# MB1167.net
KiCad netlist of a schematic drawn in Altium Designer
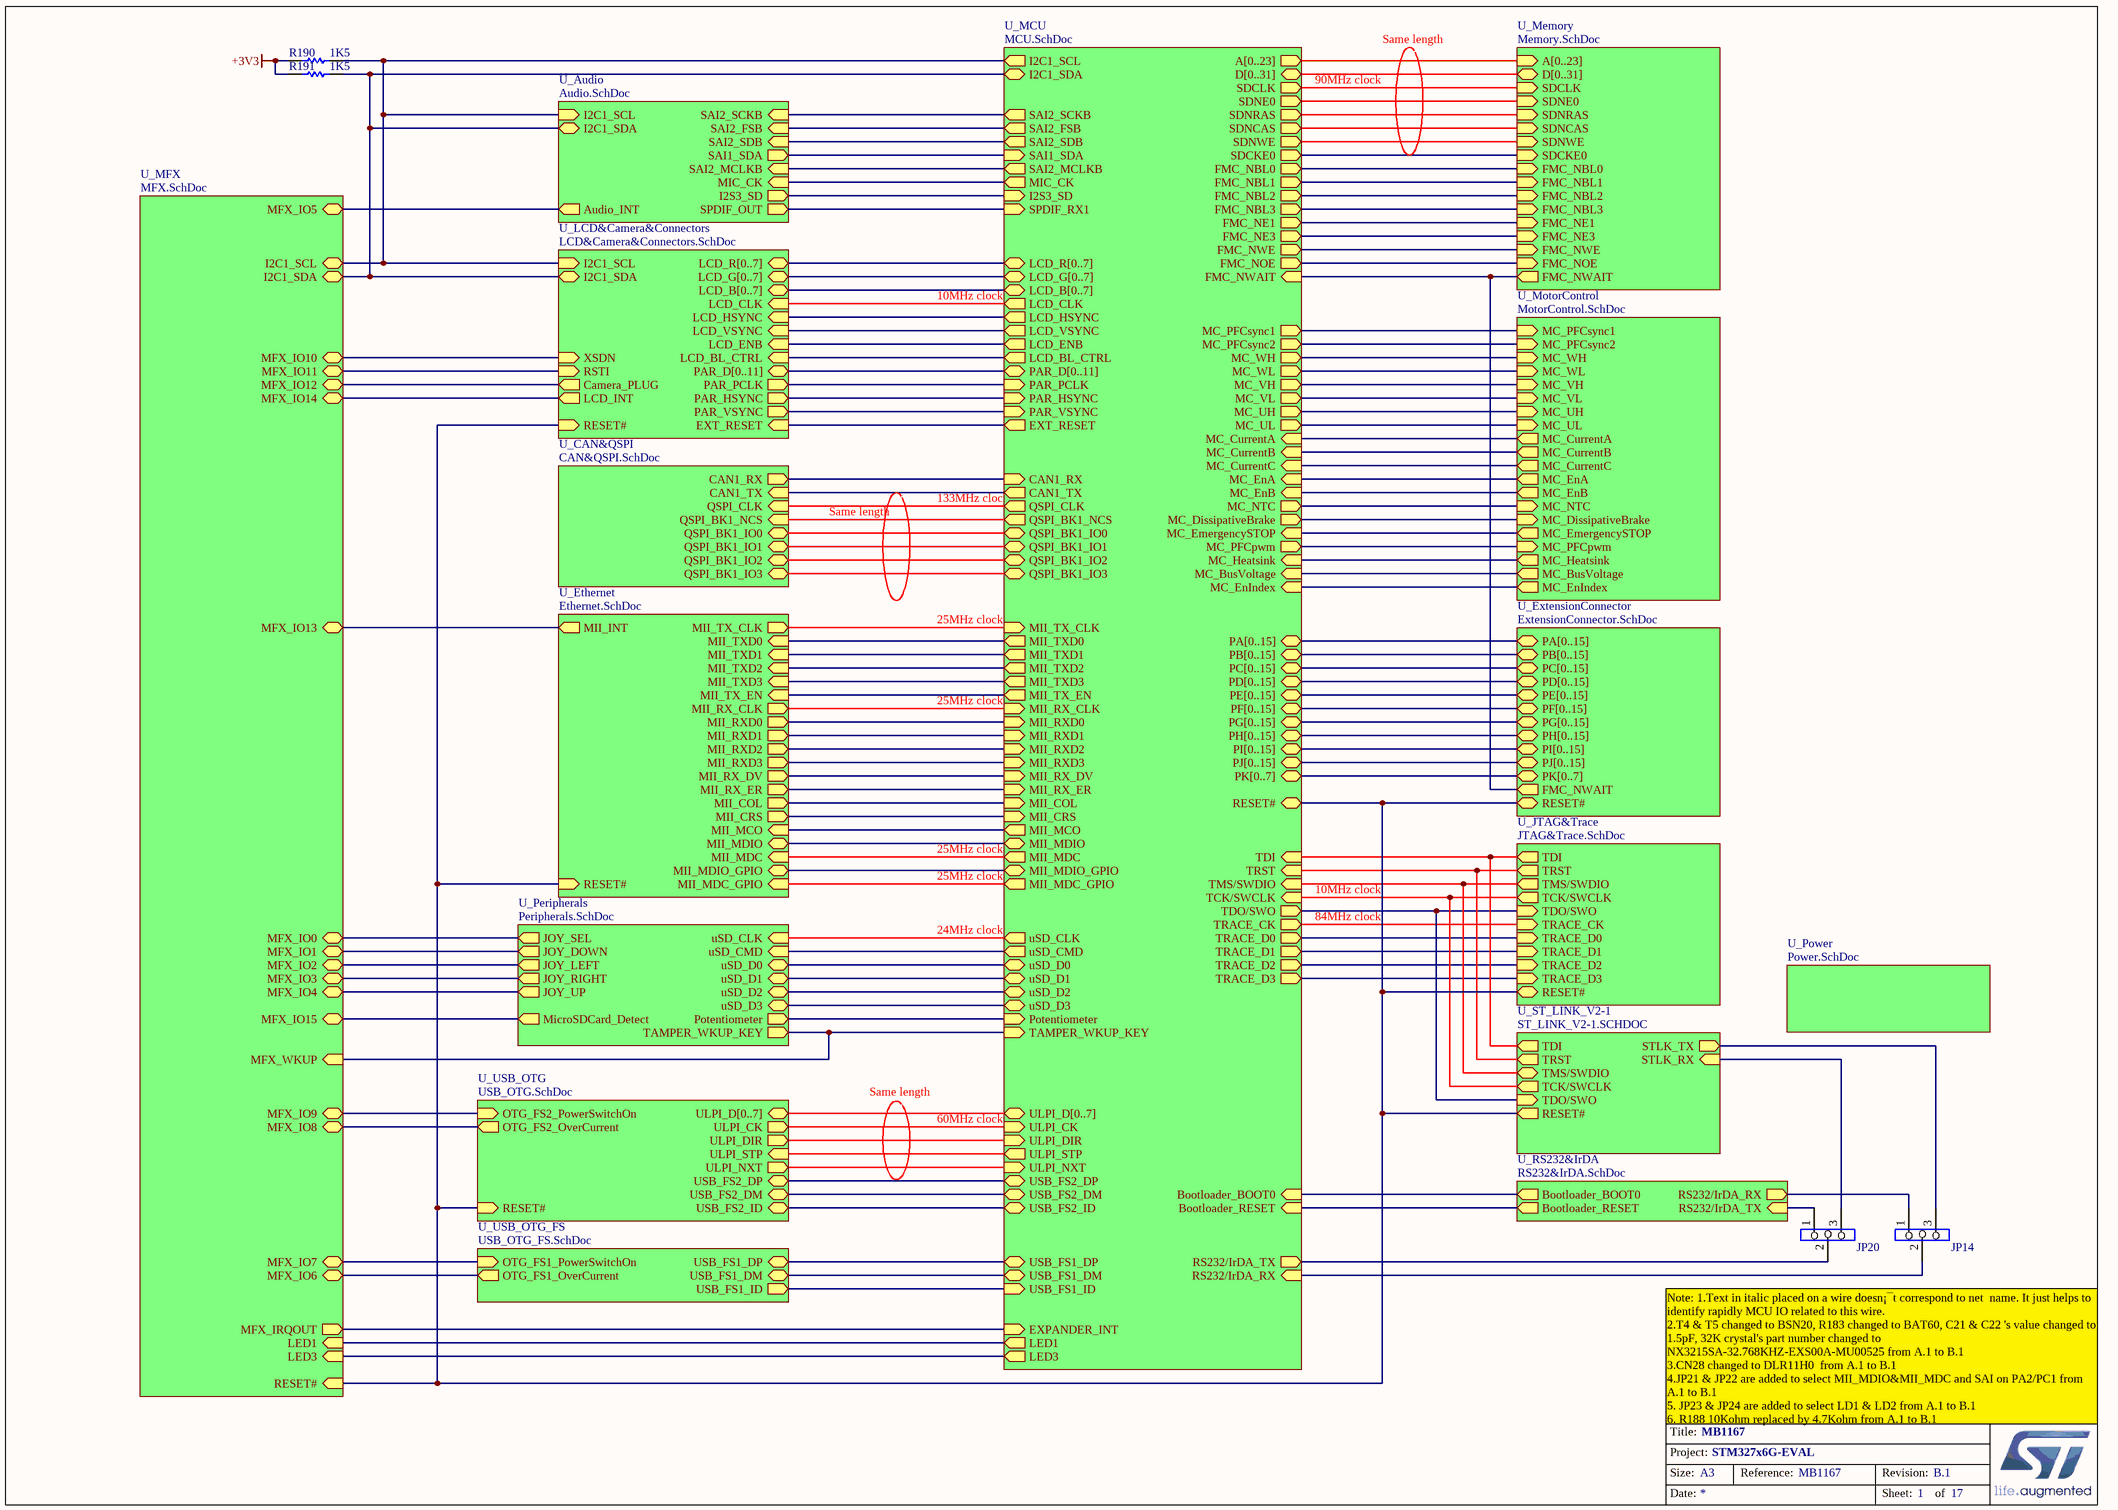
[diagram p0: MB1167.SchDoc]

(export (version "E")
  (design (tool "Eeschema 10.0.6"))
  (components
    (comp (ref "JP14") (value "~") (footprint "SIP3") (libsource (lib "STR910_SCHLIB") (part "Jumper3")))
    (comp (ref "JP20") (value "~") (footprint "SIP3") (libsource (lib "STR910_SCHLIB") (part "Jumper3")))
    (comp (ref "R190")
      (value "1K5")
      (footprint "0603R")
      (description "Resistor")
      (fields (field (name "PUBLISHER") "Altium Limited"))
      (libsource (lib "Miscellaneous Devices") (part "Res1"))
    )
    (comp (ref "R191")
      (value "1K5")
      (footprint "0603R")
      (description "Resistor")
      (fields (field (name "PUBLISHER") "Altium Limited"))
      (libsource (lib "Miscellaneous Devices") (part "Res1"))
    )
  )
  (nets
    (net (code "1") (name "+3V3") (class "Default")
      (node (ref "R190") (pin "1") (pinfunction "1_1") (pintype "passive"))
      (node (ref "R191") (pin "1") (pinfunction "1_1") (pintype "passive"))
    )
    (net (code "20") (name "/I2C1_SCL") (class "Default")
      (node (ref "R190") (pin "2") (pinfunction "2_2") (pintype "passive"))
    )
    (net (code "21") (name "/I2C1_SDA") (class "Default")
      (node (ref "R191") (pin "2") (pinfunction "2_2") (pintype "passive"))
    )
    (net (code "112") (name "/RS232{slash}IrDA_RX") (class "Default")
      (node (ref "JP14") (pin "1") (pintype "passive"))
    )
    (net (code "113") (name "/RS232{slash}IrDA_RX_1") (class "Default")
      (node (ref "JP14") (pin "2") (pintype "passive"))
    )
    (net (code "114") (name "/RS232{slash}IrDA_TX") (class "Default")
      (node (ref "JP20") (pin "1") (pintype "passive"))
    )
    (net (code "115") (name "/RS232{slash}IrDA_TX_1") (class "Default")
      (node (ref "JP20") (pin "2") (pintype "passive"))
    )
    (net (code "128") (name "/STLK_RX") (class "Default") (node (ref "JP20") (pin "3") (pintype "passive")))
    (net (code "129") (name "/STLK_TX") (class "Default") (node (ref "JP14") (pin "3") (pintype "passive")))
  )
)
